# 00A-95.net
KiCad netlist of a schematic drawn in EAGLE
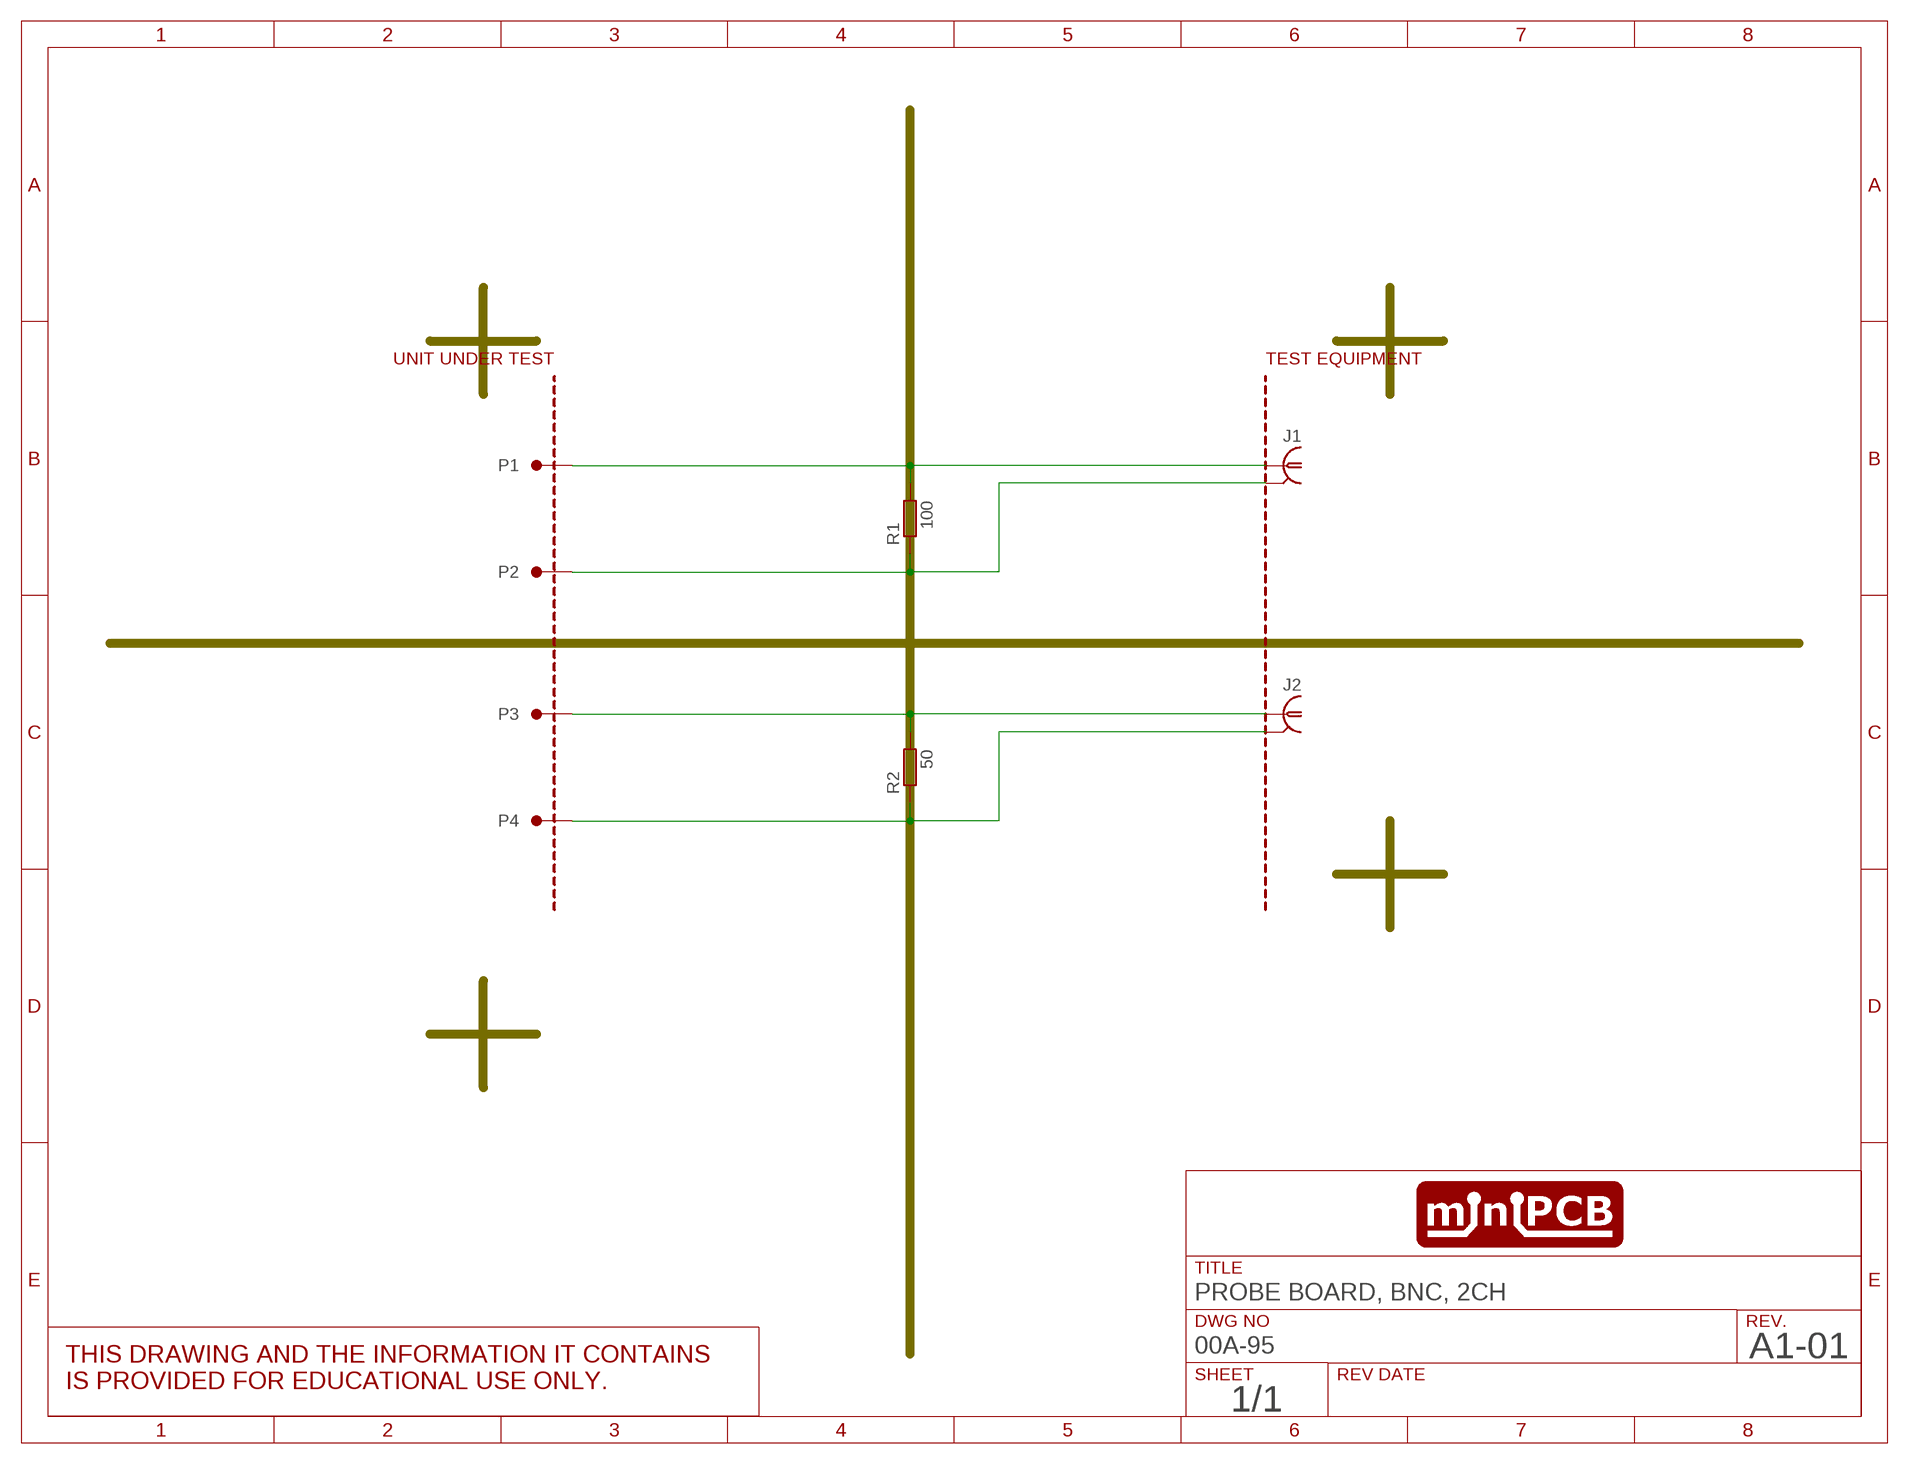
[diagram p0: schematic, sheet 1]

(export (version "E")
  (design (tool "Eeschema 10.0.6"))
  (components
    (comp (ref "J1")
      (value "BNC_RA")
      (footprint "eagle-import:BNC_RIGHTANGLE")
      (libsource (lib "eagle-import") (part "BNC_RA"))
    )
    (comp (ref "J2")
      (value "BNC_RA")
      (footprint "eagle-import:BNC_RIGHTANGLE")
      (libsource (lib "eagle-import") (part "BNC_RA"))
    )
    (comp (ref "P1")
      (value "PINS_124AWG-NOTEXT")
      (footprint "eagle-import:PINS_1_1MM-NOTEXT")
      (libsource (lib "eagle-import") (part "PINS_124AWG-NOTEXT"))
    )
    (comp (ref "P2")
      (value "PINS_124AWG-NOTEXT")
      (footprint "eagle-import:PINS_1_1MM-NOTEXT")
      (libsource (lib "eagle-import") (part "PINS_124AWG-NOTEXT"))
    )
    (comp (ref "P3")
      (value "PINS_124AWG-NOTEXT")
      (footprint "eagle-import:PINS_1_1MM-NOTEXT")
      (libsource (lib "eagle-import") (part "PINS_124AWG-NOTEXT"))
    )
    (comp (ref "P4")
      (value "PINS_124AWG-NOTEXT")
      (footprint "eagle-import:PINS_1_1MM-NOTEXT")
      (libsource (lib "eagle-import") (part "PINS_124AWG-NOTEXT"))
    )
    (comp (ref "PCB1")
      (value "MINIPCB_0P50X50")
      (footprint "eagle-import:MINIPCB_0P_50X50MM")
      (fields
        (field (name "CIRCUIT_CATEGORY") "miniPCB, TEST BOARDS")
        (field (name "PART_NUMBER") "00A-95-A1-01")
        (field (name "REVISION") "A1")
        (field (name "TITLE") "PROBE BOARD, BNC, 2CH")
      )
      (libsource (lib "eagle-import") (part "MINIPCB_0P50X50"))
    )
    (comp (ref "R1")
      (value "100")
      (footprint "eagle-import:R0805")
      (libsource (lib "eagle-import") (part "RESISTORSMD"))
    )
    (comp (ref "R2")
      (value "50")
      (footprint "eagle-import:R0805")
      (libsource (lib "eagle-import") (part "RESISTORSMD"))
    )
  )
  (nets
    (net (code "1") (name "Net-(J1-GND)") (class "Default")
      (node (ref "J1") (pin "2") (pinfunction "GND_2") (pintype "power_in"))
      (node (ref "P2") (pin "1") (pinfunction "1_1") (pintype "bidirectional"))
      (node (ref "P2") (pin "2") (pinfunction "1_2") (pintype "bidirectional"))
      (node (ref "R1") (pin "1") (pinfunction "1_1") (pintype "passive"))
    )
    (net (code "2") (name "Net-(J1-Pad1)") (class "Default")
      (node (ref "J1") (pin "1") (pinfunction "1_1") (pintype "passive"))
      (node (ref "P1") (pin "1") (pinfunction "1_1") (pintype "bidirectional"))
      (node (ref "P1") (pin "2") (pinfunction "1_2") (pintype "bidirectional"))
      (node (ref "R1") (pin "2") (pinfunction "2_2") (pintype "passive"))
    )
    (net (code "3") (name "Net-(J2-GND)") (class "Default")
      (node (ref "J2") (pin "2") (pinfunction "GND_2") (pintype "power_in"))
      (node (ref "P4") (pin "1") (pinfunction "1_1") (pintype "bidirectional"))
      (node (ref "P4") (pin "2") (pinfunction "1_2") (pintype "bidirectional"))
      (node (ref "R2") (pin "1") (pinfunction "1_1") (pintype "passive"))
    )
    (net (code "4") (name "Net-(J2-Pad1)") (class "Default")
      (node (ref "J2") (pin "1") (pinfunction "1_1") (pintype "passive"))
      (node (ref "P3") (pin "1") (pinfunction "1_1") (pintype "bidirectional"))
      (node (ref "P3") (pin "2") (pinfunction "1_2") (pintype "bidirectional"))
      (node (ref "R2") (pin "2") (pinfunction "2_2") (pintype "passive"))
    )
  )
)
